# 06_SM_1232_AQ2.net
KiCad netlist of a schematic drawn in Altium Designer
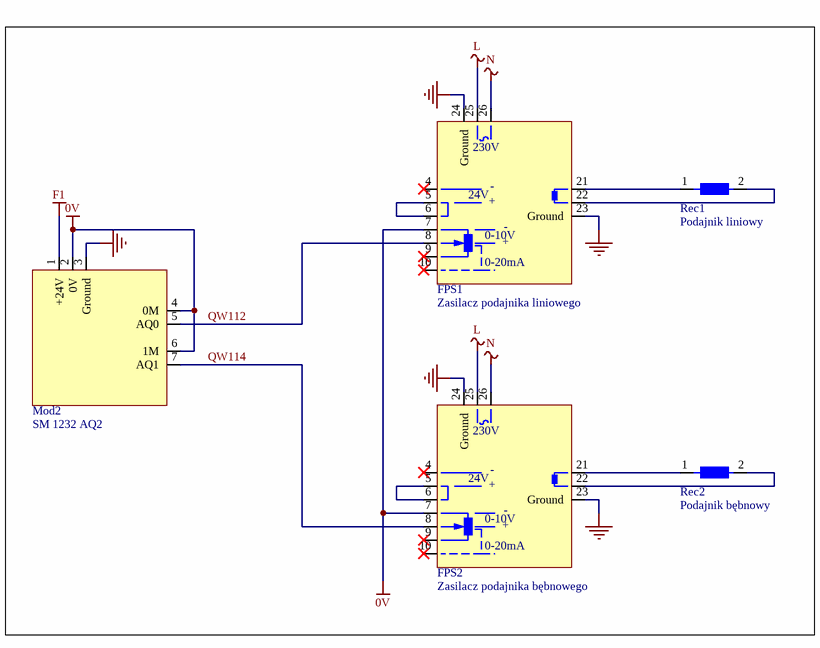
[diagram p0: [06] SM 1232 AQ2.SchDoc]

(export (version "E")
  (design (tool "Eeschema 10.0.6"))
  (components
    (comp (ref "FPS1")
      (value "Zasilacz podajnika liniowego")
      (libsource (lib "Schlib1") (part "Feed power supply"))
    )
    (comp (ref "FPS2")
      (value "Zasilacz podajnika bębnowego")
      (libsource (lib "Schlib1") (part "Feed power supply"))
    )
    (comp (ref "Mod2") (value "SM 1232 AQ2") (libsource (lib "Schlib1") (part "SM 1232 AQ2")))
    (comp (ref "Rec1") (value "Podajnik liniowy") (libsource (lib "Schlib1") (part "Receiver")))
    (comp (ref "Rec2") (value "Podajnik bębnowy") (libsource (lib "Schlib1") (part "Receiver")))
  )
  (nets
    (net (code "1") (name "/QW112") (class "Default")
      (node (ref "FPS1") (pin "8") (pinfunction "potentiometer_q_8") (pintype "passive"))
      (node (ref "Mod2") (pin "5") (pinfunction "AQ0_5") (pintype "passive"))
    )
    (net (code "2") (name "/QW114") (class "Default")
      (node (ref "FPS2") (pin "8") (pinfunction "potentiometer_q_8") (pintype "passive"))
      (node (ref "Mod2") (pin "7") (pinfunction "AQ1_7") (pintype "passive"))
    )
    (net (code "3") (name "0V") (class "Default")
      (node (ref "FPS1") (pin "7") (pinfunction "potentiometer_0V_7") (pintype "passive"))
      (node (ref "FPS2") (pin "7") (pinfunction "potentiometer_0V_7") (pintype "passive"))
      (node (ref "Mod2") (pin "2") (pinfunction "0V_2") (pintype "passive"))
      (node (ref "Mod2") (pin "4") (pinfunction "0M_4") (pintype "passive"))
      (node (ref "Mod2") (pin "6") (pinfunction "1M_6") (pintype "passive"))
    )
    (net (code "4") (name "F1") (class "Default")
      (node (ref "Mod2") (pin "1") (pinfunction "+24V_1") (pintype "passive"))
    )
    (net (code "5") (name "GND") (class "Default")
      (node (ref "FPS1") (pin "23") (pinfunction "Ground_23") (pintype "passive"))
      (node (ref "FPS1") (pin "24") (pinfunction "Ground_24") (pintype "passive"))
      (node (ref "FPS2") (pin "23") (pinfunction "Ground_23") (pintype "passive"))
      (node (ref "FPS2") (pin "24") (pinfunction "Ground_24") (pintype "passive"))
      (node (ref "Mod2") (pin "3") (pinfunction "Ground_3") (pintype "passive"))
    )
    (net (code "6") (name "L") (class "Default")
      (node (ref "FPS1") (pin "25") (pinfunction "Line_25") (pintype "passive"))
      (node (ref "FPS2") (pin "25") (pinfunction "Line_25") (pintype "passive"))
    )
    (net (code "7") (name "N") (class "Default")
      (node (ref "FPS1") (pin "26") (pinfunction "Line_26") (pintype "passive"))
      (node (ref "FPS2") (pin "26") (pinfunction "Line_26") (pintype "passive"))
    )
    (net (code "8") (name "Net-(FPS1-24V)") (class "Default")
      (node (ref "FPS1") (pin "5") (pinfunction "24V_5") (pintype "passive"))
      (node (ref "FPS1") (pin "6") (pinfunction "??_6") (pintype "passive"))
    )
    (net (code "9") (name "Net-(FPS1-Feed-Pad21)") (class "Default")
      (node (ref "FPS1") (pin "21") (pinfunction "Feed_21") (pintype "passive"))
      (node (ref "Rec1") (pin "1") (pinfunction "1_1") (pintype "passive"))
    )
    (net (code "10") (name "Net-(FPS1-Feed-Pad22)") (class "Default")
      (node (ref "FPS1") (pin "22") (pinfunction "Feed_22") (pintype "passive"))
      (node (ref "Rec1") (pin "2") (pinfunction "2_2") (pintype "passive"))
    )
    (net (code "11") (name "Net-(FPS2-24V)") (class "Default")
      (node (ref "FPS2") (pin "5") (pinfunction "24V_5") (pintype "passive"))
      (node (ref "FPS2") (pin "6") (pinfunction "??_6") (pintype "passive"))
    )
    (net (code "12") (name "Net-(FPS2-Feed-Pad21)") (class "Default")
      (node (ref "FPS2") (pin "21") (pinfunction "Feed_21") (pintype "passive"))
      (node (ref "Rec2") (pin "1") (pinfunction "1_1") (pintype "passive"))
    )
    (net (code "13") (name "Net-(FPS2-Feed-Pad22)") (class "Default")
      (node (ref "FPS2") (pin "22") (pinfunction "Feed_22") (pintype "passive"))
      (node (ref "Rec2") (pin "2") (pinfunction "2_2") (pintype "passive"))
    )
    (net (code "14") (name "unconnected-(FPS1-0V-Pad4)") (class "Default")
      (node (ref "FPS1") (pin "4") (pinfunction "0V_4") (pintype "passive+no_connect"))
    )
    (net (code "15") (name "unconnected-(FPS1-??-Pad10)") (class "Default")
      (node (ref "FPS1") (pin "10") (pinfunction "??_10") (pintype "passive+no_connect"))
    )
    (net (code "16") (name "unconnected-(FPS1-Potentiiometer_+10V-Pad9)") (class "Default")
      (node (ref "FPS1") (pin "9") (pinfunction "Potentiiometer_+10V_9") (pintype "passive+no_connect"))
    )
    (net (code "17") (name "unconnected-(FPS2-0V-Pad4)") (class "Default")
      (node (ref "FPS2") (pin "4") (pinfunction "0V_4") (pintype "passive+no_connect"))
    )
    (net (code "18") (name "unconnected-(FPS2-??-Pad10)") (class "Default")
      (node (ref "FPS2") (pin "10") (pinfunction "??_10") (pintype "passive+no_connect"))
    )
    (net (code "19") (name "unconnected-(FPS2-Potentiiometer_+10V-Pad9)") (class "Default")
      (node (ref "FPS2") (pin "9") (pinfunction "Potentiiometer_+10V_9") (pintype "passive+no_connect"))
    )
  )
)
